# Smart_Agriculture_Schematic.net
KiCad netlist of a schematic drawn in Altium Designer
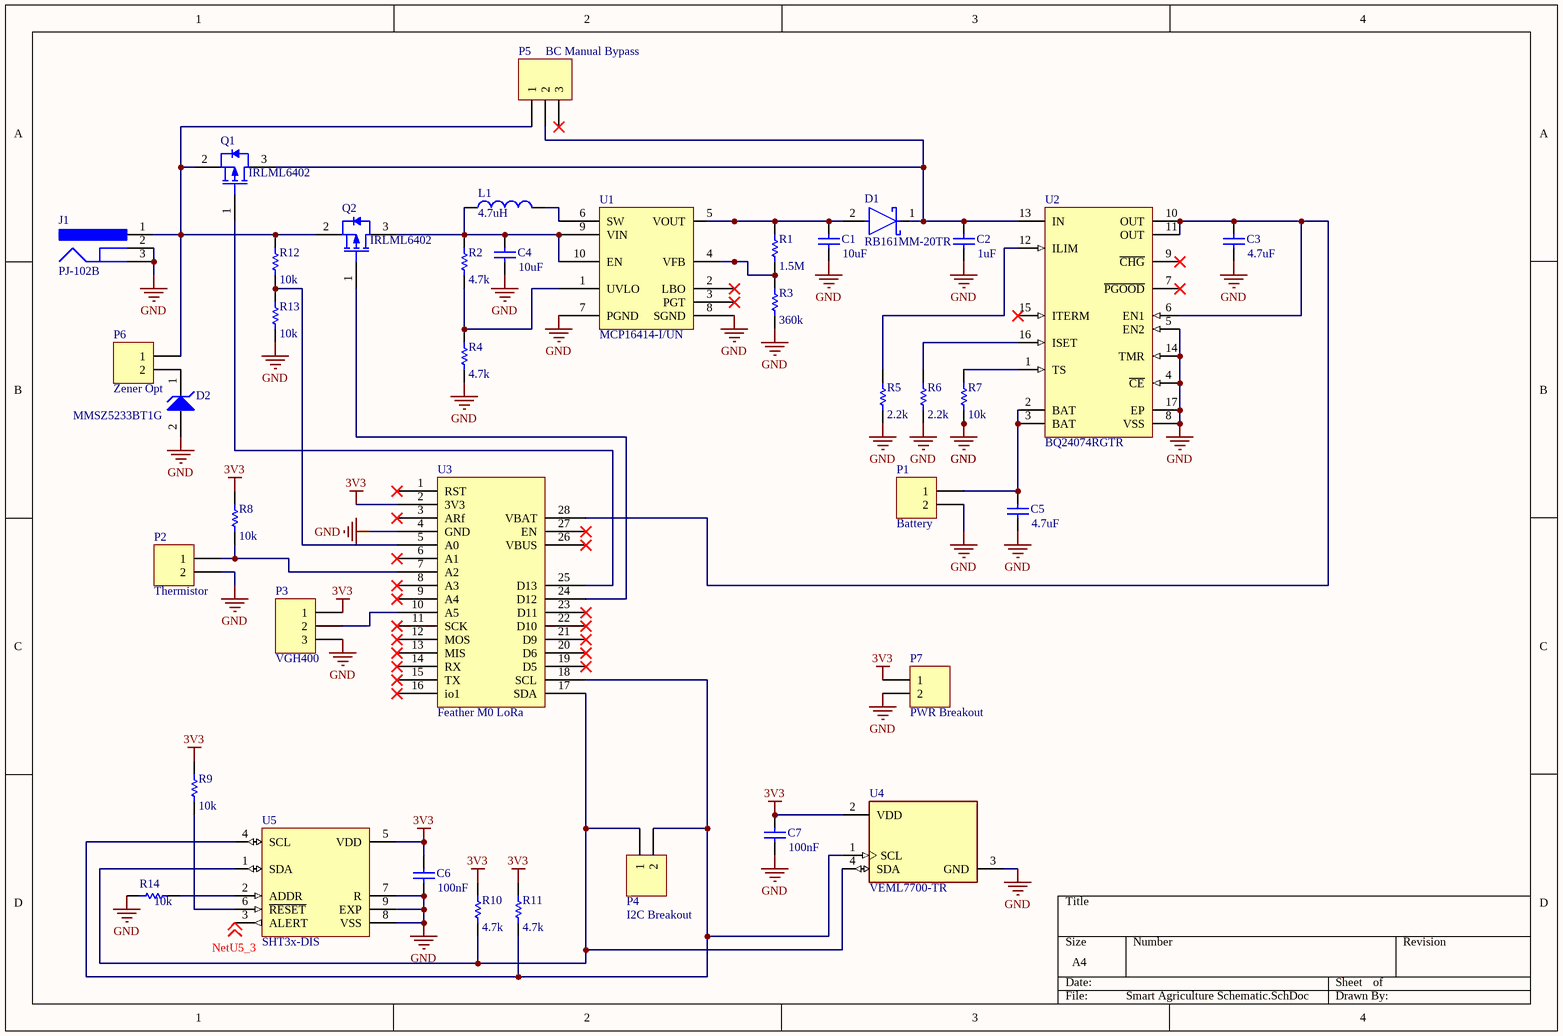
[diagram p0: Smart Agriculture Schematic.SchDoc]

(export (version "E")
  (design (tool "Eeschema 10.0.6"))
  (components
    (comp (ref "C1")
      (value "10uF")
      (footprint "1608[0603]")
      (description "Capacitor")
      (fields (field (name "PUBLISHER") "Altium Limited"))
      (libsource (lib "Miscellaneous Devices") (part "Cap"))
    )
    (comp (ref "C2")
      (value "1uF")
      (footprint "1608[0603]")
      (description "Capacitor")
      (fields (field (name "PUBLISHER") "Altium Limited"))
      (libsource (lib "Miscellaneous Devices") (part "Cap"))
    )
    (comp (ref "C3")
      (value "4.7uF")
      (footprint "1608[0603]")
      (description "Capacitor")
      (fields (field (name "PUBLISHER") "Altium Limited"))
      (libsource (lib "Miscellaneous Devices") (part "Cap"))
    )
    (comp (ref "C4")
      (value "10uF")
      (footprint "1608[0603]")
      (description "Capacitor")
      (fields (field (name "PUBLISHER") "Altium Limited"))
      (libsource (lib "Miscellaneous Devices") (part "Cap"))
    )
    (comp (ref "C5")
      (value "4.7uF")
      (footprint "1608[0603]")
      (description "Capacitor")
      (fields (field (name "PUBLISHER") "Altium Limited"))
      (libsource (lib "Miscellaneous Devices") (part "Cap"))
    )
    (comp (ref "C6")
      (value "100nF")
      (footprint "1608[0603]")
      (description "Capacitor")
      (fields (field (name "PUBLISHER") "Altium Limited"))
      (libsource (lib "Miscellaneous Devices") (part "Cap"))
    )
    (comp (ref "C7")
      (value "100nF")
      (footprint "1608[0603]")
      (description "Capacitor")
      (fields (field (name "PUBLISHER") "Altium Limited"))
      (libsource (lib "Miscellaneous Devices") (part "Cap"))
    )
    (comp (ref "D1")
      (value "RB161MM-20TR")
      (footprint "FP-PMDU-MFG")
      (description "DIODE SCHOTTKY 25V 1A PMDU")
      (fields
        (field (name "MANUFACTURER") "Rohm")
        (field (name "OCTOPART") "https://octopart.com/rb161mm-20tr-rohm-50255147")
      )
      (libsource (lib "Altium Content Vault") (part "1d6ec82d83fb6aee721767c19dac4b9"))
    )
    (comp (ref "D2")
      (value "MMSZ5233BT1G")
      (footprint "ONSC-SOD-123-2-425-04_V")
      (description "Zener Voltage Regulator, 500 mW, 2-Pin SOD-123, Pb-Free, Tape and Reel")
      (fields (field (name "MANUFACTURER") "On Semiconductor"))
      (libsource (lib "Altium Content Vault") (part "ONSC-K1A2-2"))
    )
    (comp (ref "J1")
      (value "PJ-102B")
      (footprint "CUI-PJ-102B_V")
      (fields (field (name "MANUFACTURER") "CUIInc."))
      (libsource (lib "Altium Content Vault") (part "JACK-2CD3-RN"))
    )
    (comp (ref "L1")
      (value "4.7uH")
      (footprint "1812")
      (description "Inductor")
      (fields (field (name "PUBLISHER") "Altium Limited"))
      (libsource (lib "Miscellaneous Devices") (part "Inductor"))
    )
    (comp (ref "P1")
      (value "Battery")
      (footprint "HDR1X2")
      (description "Header, 2-Pin")
      (fields (field (name "PUBLISHER") "Altium Limited"))
      (libsource (lib "") (part "Header 2_1"))
    )
    (comp (ref "P2")
      (value "Thermistor")
      (footprint "HDR1X2")
      (description "Header, 2-Pin")
      (fields (field (name "PUBLISHER") "Altium Limited"))
      (libsource (lib "") (part "Header 2_1"))
    )
    (comp (ref "P3")
      (value "VGH400")
      (footprint "HDR1X3")
      (description "Header, 3-Pin")
      (fields (field (name "PUBLISHER") "Altium Limited"))
      (libsource (lib "Miscellaneous Connectors") (part "Header 3"))
    )
    (comp (ref "P4")
      (value "I2C Breakout")
      (footprint "HDR1X2")
      (description "Header, 2-Pin")
      (fields (field (name "PUBLISHER") "Altium Limited"))
      (libsource (lib "") (part "Header 2_2"))
    )
    (comp (ref "P5")
      (value "BC Manual Bypass")
      (footprint "HDR1X3")
      (description "Header, 3-Pin")
      (fields (field (name "PUBLISHER") "Altium Limited"))
      (libsource (lib "") (part "Header 3_1"))
    )
    (comp (ref "P6")
      (value "Zener Opt")
      (footprint "HDR1X2")
      (description "Header, 2-Pin")
      (fields (field (name "PUBLISHER") "Altium Limited"))
      (libsource (lib "") (part "Header 2_1"))
    )
    (comp (ref "P7")
      (value "PWR Breakout")
      (footprint "HDR1X2")
      (description "Header, 2-Pin")
      (fields (field (name "PUBLISHER") "Altium Limited"))
      (libsource (lib "Miscellaneous Connectors") (part "Header 2"))
    )
    (comp (ref "Q1")
      (value "IRLML6402")
      (footprint "INTR-SOT-23-3_V")
      (fields (field (name "MANUFACTURER") "International Rectifier"))
      (libsource (lib "Altium Content Vault") (part "PEMOS-GSD-3"))
    )
    (comp (ref "Q2")
      (value "IRLML6402")
      (footprint "INTR-SOT-23-3_V")
      (fields (field (name "MANUFACTURER") "International Rectifier"))
      (libsource (lib "Altium Content Vault") (part "PEMOS-GSD-3"))
    )
    (comp (ref "R1")
      (value "1.5M")
      (footprint "1608[0603]")
      (description "Resistor")
      (fields (field (name "PUBLISHER") "Altium Limited"))
      (libsource (lib "Miscellaneous Devices") (part "Res1"))
    )
    (comp (ref "R2")
      (value "4.7k")
      (footprint "1608[0603]")
      (description "Resistor")
      (fields (field (name "PUBLISHER") "Altium Limited"))
      (libsource (lib "Miscellaneous Devices") (part "Res1"))
    )
    (comp (ref "R3")
      (value "360k")
      (footprint "1608[0603]")
      (description "Resistor")
      (fields (field (name "PUBLISHER") "Altium Limited"))
      (libsource (lib "Miscellaneous Devices") (part "Res1"))
    )
    (comp (ref "R4")
      (value "4.7k")
      (footprint "1608[0603]")
      (description "Resistor")
      (fields (field (name "PUBLISHER") "Altium Limited"))
      (libsource (lib "Miscellaneous Devices") (part "Res1"))
    )
    (comp (ref "R5")
      (value "2.2k")
      (footprint "1608[0603]")
      (description "Resistor")
      (fields (field (name "PUBLISHER") "Altium Limited"))
      (libsource (lib "Miscellaneous Devices") (part "Res1"))
    )
    (comp (ref "R6")
      (value "2.2k")
      (footprint "1608[0603]")
      (description "Resistor")
      (fields (field (name "PUBLISHER") "Altium Limited"))
      (libsource (lib "Miscellaneous Devices") (part "Res1"))
    )
    (comp (ref "R7")
      (value "10k")
      (footprint "1608[0603]")
      (description "Resistor")
      (fields (field (name "PUBLISHER") "Altium Limited"))
      (libsource (lib "Miscellaneous Devices") (part "Res1"))
    )
    (comp (ref "R8")
      (value "10k")
      (footprint "1608[0603]")
      (description "Resistor")
      (fields (field (name "PUBLISHER") "Altium Limited"))
      (libsource (lib "Miscellaneous Devices") (part "Res1"))
    )
    (comp (ref "R9")
      (value "10k")
      (footprint "1608[0603]")
      (description "Resistor")
      (fields (field (name "PUBLISHER") "Altium Limited"))
      (libsource (lib "Miscellaneous Devices") (part "Res1"))
    )
    (comp (ref "R10")
      (value "4.7k")
      (footprint "1608[0603]")
      (description "Resistor")
      (fields (field (name "PUBLISHER") "Altium Limited"))
      (libsource (lib "Miscellaneous Devices") (part "Res1"))
    )
    (comp (ref "R11")
      (value "4.7k")
      (footprint "1608[0603]")
      (description "Resistor")
      (fields (field (name "PUBLISHER") "Altium Limited"))
      (libsource (lib "Miscellaneous Devices") (part "Res1"))
    )
    (comp (ref "R12")
      (value "10k")
      (footprint "1608[0603]")
      (description "Resistor")
      (fields (field (name "Comment") "Res1") (field (name "PUBLISHER") "Altium Limited"))
      (libsource (lib "Miscellaneous Devices") (part "Res1"))
    )
    (comp (ref "R13")
      (value "10k")
      (footprint "1608[0603]")
      (description "Resistor")
      (fields (field (name "Comment") "Res1") (field (name "PUBLISHER") "Altium Limited"))
      (libsource (lib "Miscellaneous Devices") (part "Res1"))
    )
    (comp (ref "R14")
      (value "10k")
      (footprint "1608[0603]")
      (description "Resistor")
      (fields (field (name "PUBLISHER") "Altium Limited"))
      (libsource (lib "Miscellaneous Devices") (part "Res1"))
    )
    (comp (ref "U1")
      (value "MCP16414-I/UN")
      (footprint "MSOP10_UN_MCH")
      (libsource (lib "MCP16414-IUN") (part "Component_1"))
    )
    (comp (ref "U2")
      (value "BQ24074RGTR")
      (footprint "RGT0016C_V")
      (fields (field (name "MANUFACTURER") "Texas Instruments"))
      (libsource (lib "Altium Content Vault") (part "TI-BQ24074RGT16-1700X1700TP"))
    )
    (comp (ref "U3")
      (value "Feather M0 LoRa")
      (footprint "FeatherM0LoRa")
      (libsource (lib "FeatherM0LoRa") (part "Feather M0 LoRa"))
    )
    (comp (ref "U4")
      (value "VEML7700-TR")
      (footprint "FP-6_550-5300_02-4-MFG")
      (description "SENSOR OPT 545NM AMBIENT 4SMD")
      (fields
        (field (name "OCTOPART") "https://octopart.com/veml7700-tr-vishay-70519713")
        (field (name "MANUFACTURER") "Vishay")
      )
      (libsource (lib "Altium Content Vault") (part "910e2da346148eee15a6bcb182505dc"))
    )
    (comp (ref "U5")
      (value "SHT3x-DIS")
      (footprint "SHT3x")
      (libsource (lib "SHT31-DIS-B2.5KS") (part "SHT3x-DIS"))
    )
  )
  (nets
    (net (code "1") (name "3V3") (class "Default")
      (node (ref "C6") (pin "2") (pinfunction "2_2") (pintype "passive"))
      (node (ref "C7") (pin "2") (pinfunction "2_2") (pintype "passive"))
      (node (ref "P3") (pin "1") (pinfunction "1_1") (pintype "passive"))
      (node (ref "P7") (pin "1") (pinfunction "1_1") (pintype "passive"))
      (node (ref "R10") (pin "2") (pinfunction "2_2") (pintype "passive"))
      (node (ref "R11") (pin "2") (pinfunction "2_2") (pintype "passive"))
      (node (ref "R8") (pin "2") (pinfunction "2_2") (pintype "passive"))
      (node (ref "R9") (pin "2") (pinfunction "2_2") (pintype "passive"))
      (node (ref "U3") (pin "2") (pinfunction "3V3_2") (pintype "passive"))
      (node (ref "U4") (pin "2") (pinfunction "VDD_2") (pintype "power_in"))
      (node (ref "U5") (pin "5") (pinfunction "VDD_5") (pintype "power_in"))
    )
    (net (code "2") (name "GND") (class "Default")
      (node (ref "C1") (pin "1") (pinfunction "1_1") (pintype "passive"))
      (node (ref "C2") (pin "1") (pinfunction "1_1") (pintype "passive"))
      (node (ref "C3") (pin "1") (pinfunction "1_1") (pintype "passive"))
      (node (ref "C4") (pin "1") (pinfunction "1_1") (pintype "passive"))
      (node (ref "C5") (pin "1") (pinfunction "1_1") (pintype "passive"))
      (node (ref "C6") (pin "1") (pinfunction "1_1") (pintype "passive"))
      (node (ref "C7") (pin "1") (pinfunction "1_1") (pintype "passive"))
      (node (ref "D2") (pin "2") (pinfunction "A_2") (pintype "passive"))
      (node (ref "J1") (pin "2") (pinfunction "2_2") (pintype "passive"))
      (node (ref "J1") (pin "3") (pinfunction "3_3") (pintype "passive"))
      (node (ref "P1") (pin "2") (pinfunction "2_2") (pintype "passive"))
      (node (ref "P2") (pin "2") (pinfunction "2_2") (pintype "passive"))
      (node (ref "P3") (pin "3") (pinfunction "3_3") (pintype "passive"))
      (node (ref "P7") (pin "2") (pinfunction "2_2") (pintype "passive"))
      (node (ref "R13") (pin "1") (pinfunction "1_1") (pintype "passive"))
      (node (ref "R14") (pin "1") (pinfunction "1_1") (pintype "passive"))
      (node (ref "R3") (pin "1") (pinfunction "1_1") (pintype "passive"))
      (node (ref "R4") (pin "1") (pinfunction "1_1") (pintype "passive"))
      (node (ref "R5") (pin "1") (pinfunction "1_1") (pintype "passive"))
      (node (ref "R6") (pin "1") (pinfunction "1_1") (pintype "passive"))
      (node (ref "R7") (pin "1") (pinfunction "1_1") (pintype "passive"))
      (node (ref "U1") (pin "7") (pinfunction "PGND_7") (pintype "passive"))
      (node (ref "U1") (pin "8") (pinfunction "SGND_8") (pintype "passive"))
      (node (ref "U2") (pin "14") (pinfunction "TMR_14") (pintype "input"))
      (node (ref "U2") (pin "17") (pinfunction "EP_17") (pintype "power_in"))
      (node (ref "U2") (pin "4") (pinfunction "~{CE}_4") (pintype "input"))
      (node (ref "U2") (pin "5") (pinfunction "EN2_5") (pintype "input"))
      (node (ref "U2") (pin "8") (pinfunction "VSS_8") (pintype "power_in"))
      (node (ref "U3") (pin "4") (pinfunction "GND_4") (pintype "passive"))
      (node (ref "U4") (pin "3") (pinfunction "GND_3") (pintype "power_in"))
      (node (ref "U5") (pin "7") (pinfunction "R_7") (pintype "passive"))
      (node (ref "U5") (pin "8") (pinfunction "VSS_8") (pintype "power_in"))
      (node (ref "U5") (pin "9") (pinfunction "EXP_9") (pintype "passive"))
    )
    (net (code "3") (name "Net-(C5-Pad2)") (class "Default")
      (node (ref "C5") (pin "2") (pinfunction "2_2") (pintype "passive"))
      (node (ref "P1") (pin "1") (pinfunction "1_1") (pintype "passive"))
      (node (ref "U2") (pin "2") (pinfunction "BAT_2") (pintype "power_in"))
      (node (ref "U2") (pin "3") (pinfunction "BAT_3") (pintype "power_in"))
    )
    (net (code "4") (name "Net-(D1-A)") (class "Default")
      (node (ref "C1") (pin "2") (pinfunction "2_2") (pintype "passive"))
      (node (ref "D1") (pin "2") (pinfunction "A_2") (pintype "passive"))
      (node (ref "R1") (pin "2") (pinfunction "2_2") (pintype "passive"))
      (node (ref "U1") (pin "5") (pinfunction "VOUT_5") (pintype "passive"))
    )
    (net (code "5") (name "Net-(D1-C)") (class "Default")
      (node (ref "C2") (pin "2") (pinfunction "2_2") (pintype "passive"))
      (node (ref "D1") (pin "1") (pinfunction "C_1") (pintype "passive"))
      (node (ref "P5") (pin "2") (pinfunction "2_2") (pintype "passive"))
      (node (ref "Q1") (pin "3") (pinfunction "DRAIN_3") (pintype "passive"))
      (node (ref "U2") (pin "13") (pinfunction "IN_13") (pintype "power_in"))
    )
    (net (code "6") (name "Net-(D2-K)") (class "Default")
      (node (ref "D2") (pin "1") (pinfunction "K_1") (pintype "passive"))
      (node (ref "P6") (pin "2") (pinfunction "2_2") (pintype "passive"))
    )
    (net (code "7") (name "Net-(Q1-GATE)") (class "Default")
      (node (ref "Q1") (pin "1") (pinfunction "GATE_1") (pintype "passive"))
      (node (ref "U3") (pin "25") (pinfunction "D13_25") (pintype "passive"))
    )
    (net (code "8") (name "Net-(Q1-SOURCE)") (class "Default")
      (node (ref "J1") (pin "1") (pinfunction "1_1") (pintype "passive"))
      (node (ref "P5") (pin "1") (pinfunction "1_1") (pintype "passive"))
      (node (ref "P6") (pin "1") (pinfunction "1_1") (pintype "passive"))
      (node (ref "Q1") (pin "2") (pinfunction "SOURCE_2") (pintype "passive"))
      (node (ref "Q2") (pin "2") (pinfunction "SOURCE_2") (pintype "passive"))
      (node (ref "R12") (pin "2") (pinfunction "2_2") (pintype "passive"))
    )
    (net (code "9") (name "Net-(Q2-DRAIN)") (class "Default")
      (node (ref "C4") (pin "2") (pinfunction "2_2") (pintype "passive"))
      (node (ref "L1") (pin "1") (pinfunction "1_1") (pintype "passive"))
      (node (ref "Q2") (pin "3") (pinfunction "DRAIN_3") (pintype "passive"))
      (node (ref "R2") (pin "2") (pinfunction "2_2") (pintype "passive"))
      (node (ref "U1") (pin "10") (pinfunction "EN_10") (pintype "passive"))
      (node (ref "U1") (pin "9") (pinfunction "VIN_9") (pintype "passive"))
    )
    (net (code "10") (name "Net-(Q2-GATE)") (class "Default")
      (node (ref "Q2") (pin "1") (pinfunction "GATE_1") (pintype "passive"))
      (node (ref "U3") (pin "24") (pinfunction "D12_24") (pintype "passive"))
    )
    (net (code "11") (name "Net-(U1-SW)") (class "Default")
      (node (ref "L1") (pin "2") (pinfunction "2_2") (pintype "passive"))
      (node (ref "U1") (pin "6") (pinfunction "SW_6") (pintype "passive"))
    )
    (net (code "12") (name "Net-(U1-UVLO)") (class "Default")
      (node (ref "R2") (pin "1") (pinfunction "1_1") (pintype "passive"))
      (node (ref "R4") (pin "2") (pinfunction "2_2") (pintype "passive"))
      (node (ref "U1") (pin "1") (pinfunction "UVLO_1") (pintype "passive"))
    )
    (net (code "13") (name "Net-(U1-VFB)") (class "Default")
      (node (ref "R1") (pin "1") (pinfunction "1_1") (pintype "passive"))
      (node (ref "R3") (pin "2") (pinfunction "2_2") (pintype "passive"))
      (node (ref "U1") (pin "4") (pinfunction "VFB_4") (pintype "passive"))
    )
    (net (code "14") (name "Net-(U2-EN1)") (class "Default")
      (node (ref "C3") (pin "2") (pinfunction "2_2") (pintype "passive"))
      (node (ref "U2") (pin "10") (pinfunction "OUT_10") (pintype "power_in"))
      (node (ref "U2") (pin "11") (pinfunction "OUT_11") (pintype "power_in"))
      (node (ref "U2") (pin "6") (pinfunction "EN1_6") (pintype "input"))
      (node (ref "U3") (pin "28") (pinfunction "VBAT_28") (pintype "passive"))
    )
    (net (code "15") (name "Net-(U2-ILIM)") (class "Default")
      (node (ref "R5") (pin "2") (pinfunction "2_2") (pintype "passive"))
      (node (ref "U2") (pin "12") (pinfunction "ILIM_12") (pintype "input"))
    )
    (net (code "16") (name "Net-(U2-ISET)") (class "Default")
      (node (ref "R6") (pin "2") (pinfunction "2_2") (pintype "passive"))
      (node (ref "U2") (pin "16") (pinfunction "ISET_16") (pintype "input"))
    )
    (net (code "17") (name "Net-(U2-TS)") (class "Default")
      (node (ref "R7") (pin "2") (pinfunction "2_2") (pintype "passive"))
      (node (ref "U2") (pin "1") (pinfunction "TS_1") (pintype "input"))
    )
    (net (code "18") (name "Net-(U3-A0)") (class "Default")
      (node (ref "R12") (pin "1") (pinfunction "1_1") (pintype "passive"))
      (node (ref "R13") (pin "2") (pinfunction "2_2") (pintype "passive"))
      (node (ref "U3") (pin "5") (pinfunction "A0_5") (pintype "passive"))
    )
    (net (code "19") (name "Net-(U3-A2)") (class "Default")
      (node (ref "P2") (pin "1") (pinfunction "1_1") (pintype "passive"))
      (node (ref "R8") (pin "1") (pinfunction "1_1") (pintype "passive"))
      (node (ref "U3") (pin "7") (pinfunction "A2_7") (pintype "passive"))
    )
    (net (code "20") (name "Net-(U3-A5)") (class "Default")
      (node (ref "P3") (pin "2") (pinfunction "2_2") (pintype "passive"))
      (node (ref "U3") (pin "10") (pinfunction "A5_10") (pintype "passive"))
    )
    (net (code "21") (name "Net-(U3-SCL)") (class "Default")
      (node (ref "P4") (pin "2") (pinfunction "2_2") (pintype "passive"))
      (node (ref "R11") (pin "1") (pinfunction "1_1") (pintype "passive"))
      (node (ref "U3") (pin "18") (pinfunction "SCL_18") (pintype "passive"))
      (node (ref "U4") (pin "1") (pinfunction "SCL_1") (pintype "input"))
      (node (ref "U5") (pin "4") (pinfunction "SCL_4") (pintype "bidirectional"))
    )
    (net (code "22") (name "Net-(U3-SDA)") (class "Default")
      (node (ref "P4") (pin "1") (pinfunction "1_1") (pintype "passive"))
      (node (ref "R10") (pin "1") (pinfunction "1_1") (pintype "passive"))
      (node (ref "U3") (pin "17") (pinfunction "SDA_17") (pintype "passive"))
      (node (ref "U4") (pin "4") (pinfunction "SDA_4") (pintype "bidirectional"))
      (node (ref "U5") (pin "1") (pinfunction "SDA_1") (pintype "bidirectional"))
    )
    (net (code "23") (name "Net-(U5-ADDR)") (class "Default")
      (node (ref "R14") (pin "2") (pinfunction "2_2") (pintype "passive"))
      (node (ref "U5") (pin "2") (pinfunction "ADDR_2") (pintype "input"))
    )
    (net (code "24") (name "Net-(U5-~{RESET})") (class "Default")
      (node (ref "R9") (pin "1") (pinfunction "1_1") (pintype "passive"))
      (node (ref "U5") (pin "6") (pinfunction "~{RESET}_6") (pintype "input"))
    )
    (net (code "25") (name "NetU5_3") (class "Default")
      (node (ref "U5") (pin "3") (pinfunction "ALERT_3") (pintype "output"))
    )
    (net (code "26") (name "unconnected-(P5-Pad3)") (class "Default")
      (node (ref "P5") (pin "3") (pinfunction "3_3") (pintype "passive+no_connect"))
    )
    (net (code "27") (name "unconnected-(U1-LBO-Pad2)") (class "Default")
      (node (ref "U1") (pin "2") (pinfunction "LBO_2") (pintype "passive+no_connect"))
    )
    (net (code "28") (name "unconnected-(U1-PGT-Pad3)") (class "Default")
      (node (ref "U1") (pin "3") (pinfunction "PGT_3") (pintype "passive+no_connect"))
    )
    (net (code "29") (name "unconnected-(U2-ITERM-Pad15)") (class "Default")
      (node (ref "U2") (pin "15") (pinfunction "ITERM_15") (pintype "input+no_connect"))
    )
    (net (code "30") (name "unconnected-(U2-~{CHG}-Pad9)") (class "Default")
      (node (ref "U2") (pin "9") (pinfunction "~{CHG}_9") (pintype "tri_state+no_connect"))
    )
    (net (code "31") (name "unconnected-(U2-~{PGOOD}-Pad7)") (class "Default")
      (node (ref "U2") (pin "7") (pinfunction "~{PGOOD}_7") (pintype "tri_state+no_connect"))
    )
    (net (code "32") (name "unconnected-(U3-A1-Pad6)") (class "Default")
      (node (ref "U3") (pin "6") (pinfunction "A1_6") (pintype "passive+no_connect"))
    )
    (net (code "33") (name "unconnected-(U3-A3-Pad8)") (class "Default")
      (node (ref "U3") (pin "8") (pinfunction "A3_8") (pintype "passive+no_connect"))
    )
    (net (code "34") (name "unconnected-(U3-A4-Pad9)") (class "Default")
      (node (ref "U3") (pin "9") (pinfunction "A4_9") (pintype "passive+no_connect"))
    )
    (net (code "35") (name "unconnected-(U3-ARf-Pad3)") (class "Default")
      (node (ref "U3") (pin "3") (pinfunction "ARf_3") (pintype "passive+no_connect"))
    )
    (net (code "36") (name "unconnected-(U3-D5-Pad19)") (class "Default")
      (node (ref "U3") (pin "19") (pinfunction "D5_19") (pintype "passive+no_connect"))
    )
    (net (code "37") (name "unconnected-(U3-D6-Pad20)") (class "Default")
      (node (ref "U3") (pin "20") (pinfunction "D6_20") (pintype "passive+no_connect"))
    )
    (net (code "38") (name "unconnected-(U3-D9-Pad21)") (class "Default")
      (node (ref "U3") (pin "21") (pinfunction "D9_21") (pintype "passive+no_connect"))
    )
    (net (code "39") (name "unconnected-(U3-D10-Pad22)") (class "Default")
      (node (ref "U3") (pin "22") (pinfunction "D10_22") (pintype "passive+no_connect"))
    )
    (net (code "40") (name "unconnected-(U3-D11-Pad23)") (class "Default")
      (node (ref "U3") (pin "23") (pinfunction "D11_23") (pintype "passive+no_connect"))
    )
    (net (code "41") (name "unconnected-(U3-EN-Pad27)") (class "Default")
      (node (ref "U3") (pin "27") (pinfunction "EN_27") (pintype "passive+no_connect"))
    )
    (net (code "42") (name "unconnected-(U3-MIS-Pad13)") (class "Default")
      (node (ref "U3") (pin "13") (pinfunction "MIS_13") (pintype "passive+no_connect"))
    )
    (net (code "43") (name "unconnected-(U3-MOS-Pad12)") (class "Default")
      (node (ref "U3") (pin "12") (pinfunction "MOS_12") (pintype "passive+no_connect"))
    )
    (net (code "44") (name "unconnected-(U3-RST-Pad1)") (class "Default")
      (node (ref "U3") (pin "1") (pinfunction "RST_1") (pintype "passive+no_connect"))
    )
    (net (code "45") (name "unconnected-(U3-RX-Pad14)") (class "Default")
      (node (ref "U3") (pin "14") (pinfunction "RX_14") (pintype "passive+no_connect"))
    )
    (net (code "46") (name "unconnected-(U3-SCK-Pad11)") (class "Default")
      (node (ref "U3") (pin "11") (pinfunction "SCK_11") (pintype "passive+no_connect"))
    )
    (net (code "47") (name "unconnected-(U3-TX-Pad15)") (class "Default")
      (node (ref "U3") (pin "15") (pinfunction "TX_15") (pintype "passive+no_connect"))
    )
    (net (code "48") (name "unconnected-(U3-VBUS-Pad26)") (class "Default")
      (node (ref "U3") (pin "26") (pinfunction "VBUS_26") (pintype "passive+no_connect"))
    )
    (net (code "49") (name "unconnected-(U3-io1-Pad16)") (class "Default")
      (node (ref "U3") (pin "16") (pinfunction "io1_16") (pintype "passive+no_connect"))
    )
  )
)
